# MAX30101.net
KiCad netlist of a schematic drawn in Altium Designer
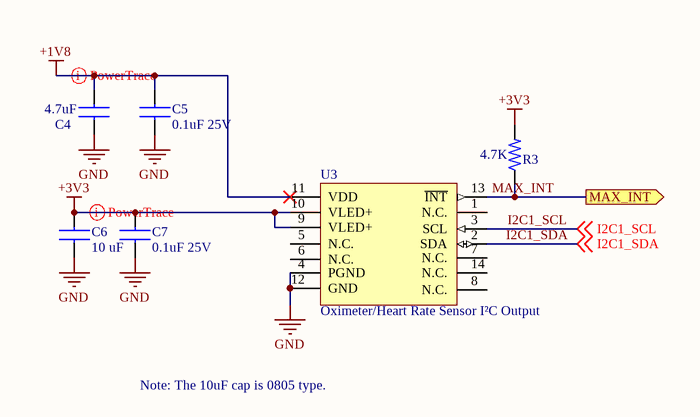
[diagram p0: MAX30101.SchDoc]

(export (version "E")
  (design (tool "Eeschema 10.0.6"))
  (components
    (comp (ref "C4")
      (value "4.7uF")
      (footprint "Chip2Pin_CAP_2_1.6x0.8")
      (description "Cap Ceramic 4.7uF 16V X7R 10% SMD 0603 125°C Paper T/R")
      (fields
        (field (name "MANUFACTURER") "Murata")
        (field (name "MANUFACTURER PART NUMBER") "GRM188Z71C475KE21D")
      )
      (libsource (lib "LPEDT_Parts") (part "GRM188Z71C475KE21D"))
    )
    (comp (ref "C5")
      (value "0.1uF 25V")
      (footprint "Chip2Pin_1.6x0.8x0.9_CAP")
      (description "Cap Ceramic 0.1uF 25V X7R 10% Pad SMD 0603 Soft Termination 125C Automotive T/R")
      (fields
        (field (name "MANUFACTURER") "Murata")
        (field (name "MANUFACTURER PART NUMBER") "GCJ188R71E104KA12D")
      )
      (libsource (lib "LPEDT_Parts") (part "GCJ188R71E104KA12D"))
    )
    (comp (ref "C6")
      (value "10 uF")
      (footprint "GRM21BR61E106KA73K")
      (description "0805 25 V 10 uF ±20% Tolerance X5R Monolithic Ceramic Chip Capacitor")
      (fields
        (field (name "MANUFACTURER") "Murata")
        (field (name "MANUFACTURER PART NUMBER") "GRM21BR61E106KA73K")
      )
      (libsource (lib "LPEDT_Parts") (part "GRM21BR61E106KA73K"))
    )
    (comp (ref "C7")
      (value "0.1uF 25V")
      (footprint "Chip2Pin_1.6x0.8x0.9_CAP")
      (description "Cap Ceramic 0.1uF 25V X7R 10% Pad SMD 0603 Soft Termination 125C Automotive T/R")
      (fields
        (field (name "MANUFACTURER") "Murata")
        (field (name "MANUFACTURER PART NUMBER") "GCJ188R71E104KA12D")
      )
      (libsource (lib "LPEDT_Parts") (part "GCJ188R71E104KA12D"))
    )
    (comp (ref "R3")
      (value "4.7K")
      (footprint "RES_0603_1608X06")
      (description "Res General Purpose Thick Film 0603 4.7k Ohm 5% 1/10W ±100ppm/°C Molded Paper T/R")
      (fields
        (field (name "MANUFACTURER") "Yageo")
        (field (name "MANUFACTURER PART NUMBER") "RC0603JR-074K7L")
      )
      (libsource (lib "LPEDT_Parts") (part "RC0603JR-074K7L"))
    )
    (comp (ref "U3")
      (value "Oximeter/Heart Rate Sensor I²C Output")
      (footprint "14-DFN-5.6x3.3")
      (description "Integrated Optical Sensor")
      (fields
        (field (name "MANUFACTURER") "Analog Devices")
        (field (name "MANUFACTURER PART NUMBER") "MAX30101EFD+T")
      )
      (libsource (lib "LPEDT_Parts") (part "MAX30101EFD+T"))
    )
  )
  (nets
    (net (code "1") (name "+1V8") (class "Default")
      (node (ref "C4") (pin "1") (pinfunction "1_1") (pintype "passive"))
      (node (ref "C5") (pin "1") (pinfunction "1_1") (pintype "passive"))
      (node (ref "U3") (pin "11") (pinfunction "VDD_11") (pintype "power_in"))
    )
    (net (code "2") (name "+3V3") (class "Default")
      (node (ref "C6") (pin "1") (pinfunction "1_1") (pintype "passive"))
      (node (ref "C7") (pin "1") (pinfunction "1_1") (pintype "passive"))
      (node (ref "R3") (pin "2") (pinfunction "2_2") (pintype "passive"))
      (node (ref "U3") (pin "10") (pinfunction "VLED+_10") (pintype "power_in"))
      (node (ref "U3") (pin "9") (pinfunction "VLED+_9") (pintype "power_in"))
    )
    (net (code "3") (name "/MAX_INT") (class "Default")
      (node (ref "R3") (pin "1") (pinfunction "1_1") (pintype "passive"))
      (node (ref "U3") (pin "13") (pinfunction "INT_13") (pintype "output"))
    )
    (net (code "4") (name "GND") (class "Default")
      (node (ref "C4") (pin "2") (pinfunction "2_2") (pintype "passive"))
      (node (ref "C5") (pin "2") (pinfunction "2_2") (pintype "passive"))
      (node (ref "C6") (pin "2") (pinfunction "2_2") (pintype "passive"))
      (node (ref "C7") (pin "2") (pinfunction "2_2") (pintype "passive"))
      (node (ref "U3") (pin "12") (pinfunction "GND_12") (pintype "passive"))
      (node (ref "U3") (pin "4") (pinfunction "PGND_4") (pintype "passive"))
    )
    (net (code "5") (name "I2C1_SCL") (class "Default")
      (node (ref "U3") (pin "3") (pinfunction "SCL_3") (pintype "input"))
    )
    (net (code "6") (name "I2C1_SDA") (class "Default")
      (node (ref "U3") (pin "2") (pinfunction "SDA_2") (pintype "bidirectional"))
    )
    (net (code "7") (name "unconnected-(U3-N.C.-Pad1)") (class "Default")
      (node (ref "U3") (pin "1") (pinfunction "N.C._1") (pintype "tri_state"))
    )
    (net (code "8") (name "unconnected-(U3-N.C.-Pad5)") (class "Default")
      (node (ref "U3") (pin "5") (pinfunction "N.C._5") (pintype "tri_state"))
    )
    (net (code "9") (name "unconnected-(U3-N.C.-Pad6)") (class "Default")
      (node (ref "U3") (pin "6") (pinfunction "N.C._6") (pintype "tri_state"))
    )
    (net (code "10") (name "unconnected-(U3-N.C.-Pad7)") (class "Default")
      (node (ref "U3") (pin "7") (pinfunction "N.C._7") (pintype "tri_state"))
    )
    (net (code "11") (name "unconnected-(U3-N.C.-Pad8)") (class "Default")
      (node (ref "U3") (pin "8") (pinfunction "N.C._8") (pintype "tri_state"))
    )
    (net (code "12") (name "unconnected-(U3-N.C.-Pad14)") (class "Default")
      (node (ref "U3") (pin "14") (pinfunction "N.C._14") (pintype "tri_state"))
    )
  )
)
